# ProDocument_AD9744_2025-01-04.net
KiCad netlist of a schematic drawn in EasyEDA Pro
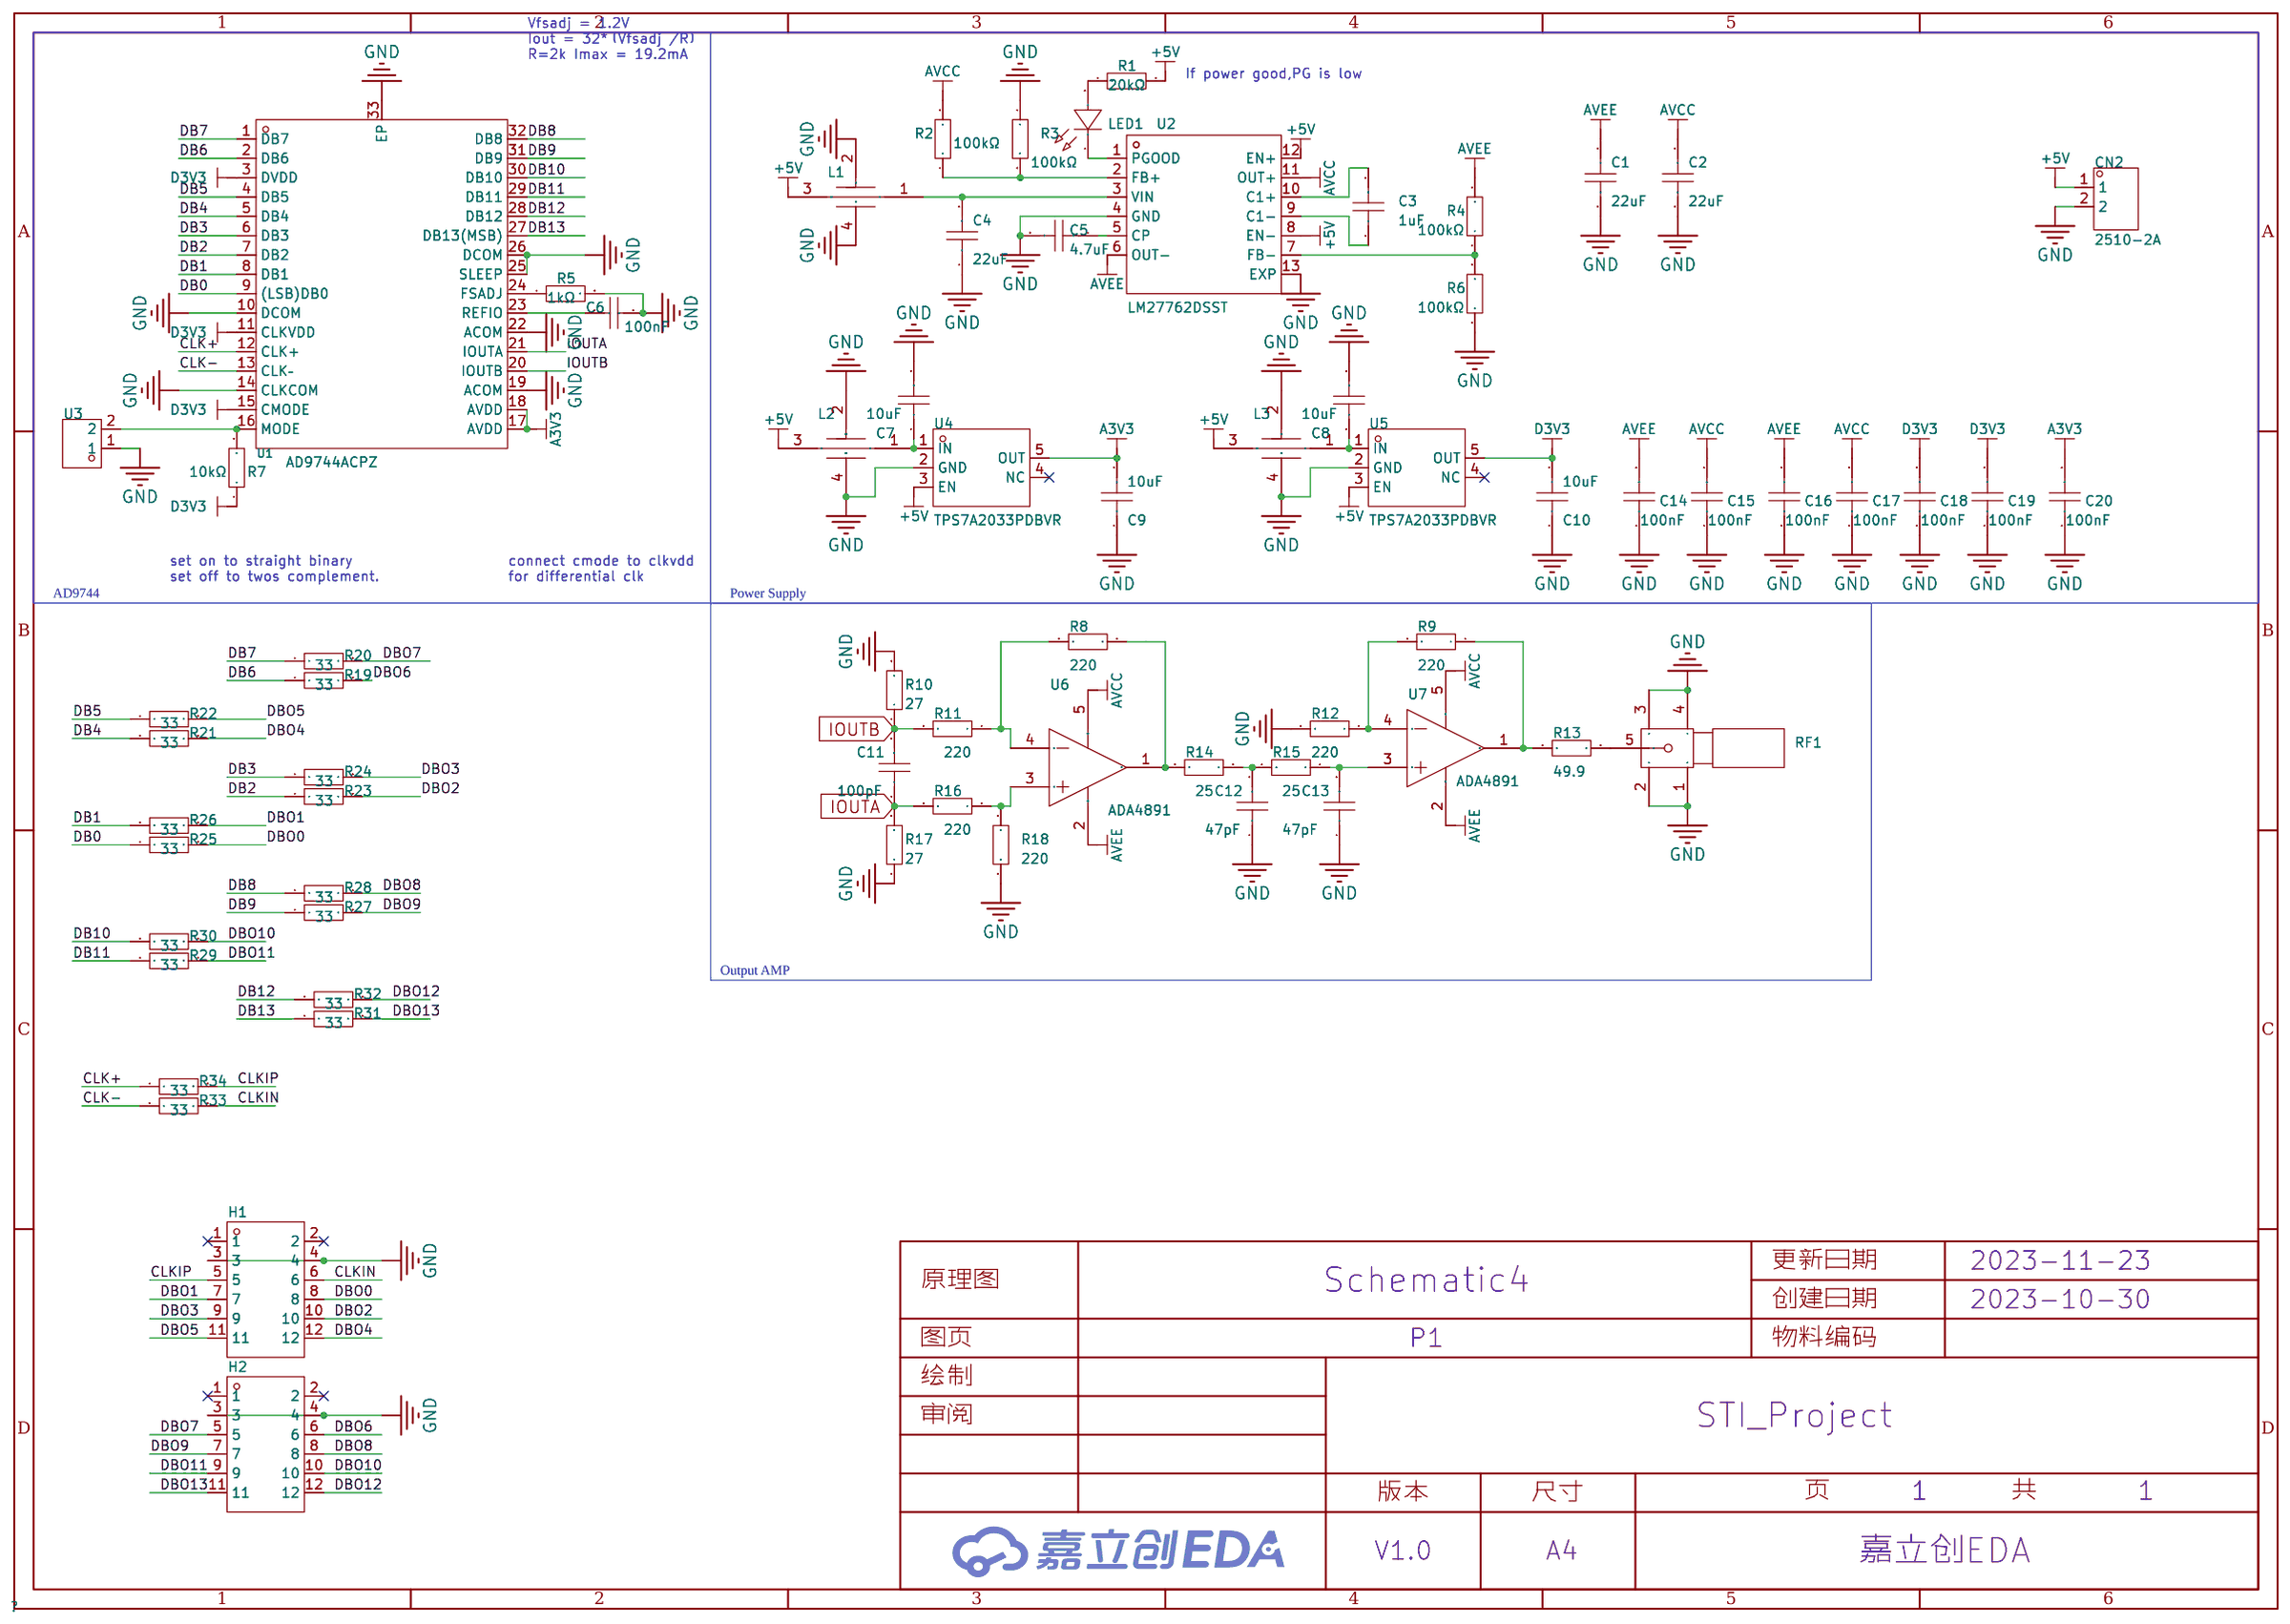
[diagram p0: schematic sheet]

(export (version "E")
  (design (tool "Eeschema 10.0.6"))
  (components
    (comp (ref "C1")
      (value "22uF")
      (footprint "easyedapro:C0805")
      (description "容值:22uF;精度:±20%;额定电压:25V;材质(温度系数):X5R;")
      (fields
        (field (name "Manufacturer Part") "CL21A226MAQNNNE")
        (field (name "Manufacturer") "SAMSUNG(三星)")
      )
      (libsource (lib "easyedapro") (part "CL21A226MAQNNNE"))
    )
    (comp (ref "C2")
      (value "22uF")
      (footprint "easyedapro:C0805")
      (description "容值:22uF;精度:±20%;额定电压:25V;材质(温度系数):X5R;")
      (fields
        (field (name "Manufacturer Part") "CL21A226MAQNNNE")
        (field (name "Manufacturer") "SAMSUNG(三星)")
      )
      (libsource (lib "easyedapro") (part "CL21A226MAQNNNE"))
    )
    (comp (ref "C3")
      (value "1uF")
      (footprint "easyedapro:C0402")
      (libsource (lib "easyedapro") (part "CapAcitance"))
    )
    (comp (ref "C4")
      (value "22uF")
      (footprint "easyedapro:C0805")
      (description "容值:22uF;精度:±20%;额定电压:25V;材质(温度系数):X5R;")
      (fields
        (field (name "Manufacturer Part") "CL21A226MAQNNNE")
        (field (name "Manufacturer") "SAMSUNG(三星)")
      )
      (libsource (lib "easyedapro") (part "CL21A226MAQNNNE"))
    )
    (comp (ref "C5")
      (value "4.7uF")
      (footprint "easyedapro:C0402")
      (libsource (lib "easyedapro") (part "CapAcitance"))
    )
    (comp (ref "C6")
      (value "100nF")
      (footprint "easyedapro:C0402")
      (description "容值:100nF;精度:±10%;额定电压:16V;材质(温度系数):X7R;")
      (fields
        (field (name "Manufacturer Part") "CL05B104KO5NNNC")
        (field (name "Manufacturer") "SAMSUNG(三星)")
      )
      (libsource (lib "easyedapro") (part "CL05B104KO5NNNC"))
    )
    (comp (ref "C7")
      (value "10uF")
      (footprint "easyedapro:C0402")
      (libsource (lib "easyedapro") (part "CapAcitance"))
    )
    (comp (ref "C8")
      (value "10uF")
      (footprint "easyedapro:C0402")
      (libsource (lib "easyedapro") (part "CapAcitance"))
    )
    (comp (ref "C9")
      (value "10uF")
      (footprint "easyedapro:C0402")
      (libsource (lib "easyedapro") (part "CapAcitance"))
    )
    (comp (ref "C10")
      (value "10uF")
      (footprint "easyedapro:C0402")
      (libsource (lib "easyedapro") (part "CapAcitance"))
    )
    (comp (ref "C11")
      (value "100pF")
      (footprint "easyedapro:C0402")
      (libsource (lib "easyedapro") (part "CapAcitance"))
    )
    (comp (ref "C12")
      (value "47pF")
      (footprint "easyedapro:C0402")
      (libsource (lib "easyedapro") (part "CapAcitance"))
    )
    (comp (ref "C13")
      (value "47pF")
      (footprint "easyedapro:C0402")
      (libsource (lib "easyedapro") (part "CapAcitance"))
    )
    (comp (ref "C14")
      (value "100nF")
      (footprint "easyedapro:C0402")
      (libsource (lib "easyedapro") (part "CapAcitance"))
    )
    (comp (ref "C15")
      (value "100nF")
      (footprint "easyedapro:C0402")
      (libsource (lib "easyedapro") (part "CapAcitance"))
    )
    (comp (ref "C16")
      (value "100nF")
      (footprint "easyedapro:C0402")
      (libsource (lib "easyedapro") (part "CapAcitance"))
    )
    (comp (ref "C17")
      (value "100nF")
      (footprint "easyedapro:C0402")
      (libsource (lib "easyedapro") (part "CapAcitance"))
    )
    (comp (ref "C18")
      (value "100nF")
      (footprint "easyedapro:C0402")
      (libsource (lib "easyedapro") (part "CapAcitance"))
    )
    (comp (ref "C19")
      (value "100nF")
      (footprint "easyedapro:C0402")
      (libsource (lib "easyedapro") (part "CapAcitance"))
    )
    (comp (ref "C20")
      (value "100nF")
      (footprint "easyedapro:C0402")
      (libsource (lib "easyedapro") (part "CapAcitance"))
    )
    (comp (ref "CN2")
      (value "2510-2A")
      (footprint "easyedapro:CONN-TH_KF2510-2A")
      (description "参考系列:-;间距:2.54mm;插针结构:1x2P;排数:1;每排PIN数:2;行距:-;安装方式:-;触头材质:-;")
      (fields (field (name "Manufacturer") "BOOMELE(博穆精密)"))
      (libsource (lib "easyedapro") (part "KF2510-2A"))
    )
    (comp (ref "H1")
      (value "DZ254W-22-12-69")
      (footprint "easyedapro:HDR-TH_12P-P2.54-H-M-R2-C6-S2.54-W12.5")
      (fields (field (name "Manufacturer") "DEALON(德艺隆)"))
      (libsource (lib "easyedapro") (part "DZ254W-22-12-69"))
    )
    (comp (ref "H2")
      (value "DZ254W-22-12-69")
      (footprint "easyedapro:HDR-TH_12P-P2.54-H-M-R2-C6-S2.54-W12.5")
      (fields (field (name "Manufacturer") "DEALON(德艺隆)"))
      (libsource (lib "easyedapro") (part "DZ254W-22-12-69"))
    )
    (comp (ref "L1")
      (value "NFM21PC104R1E3D")
      (footprint "easyedapro:CAP-SMD_4P-L2.0-W1.25")
      (description "电容量:100nF;精度:±20%;直流电阻:30mΩ;")
      (fields (field (name "Manufacturer") "muRata(村田)"))
      (libsource (lib "easyedapro") (part "NFM21PC104R1E3D"))
    )
    (comp (ref "L2")
      (value "NFM21PC104R1E3D")
      (footprint "easyedapro:CAP-SMD_4P-L2.0-W1.25")
      (description "电容量:100nF;精度:±20%;直流电阻:30mΩ;")
      (fields (field (name "Manufacturer") "muRata(村田)"))
      (libsource (lib "easyedapro") (part "NFM21PC104R1E3D"))
    )
    (comp (ref "L3")
      (value "NFM21PC104R1E3D")
      (footprint "easyedapro:CAP-SMD_4P-L2.0-W1.25")
      (description "电容量:100nF;精度:±20%;直流电阻:30mΩ;")
      (fields (field (name "Manufacturer") "muRata(村田)"))
      (libsource (lib "easyedapro") (part "NFM21PC104R1E3D"))
    )
    (comp (ref "LED1")
      (value "VLMTG1401-GS08")
      (footprint "easyedapro:LED0603-RD_GREEN")
      (description "发光颜色:翠绿;二极管配置:-;主波长:525nm;色温:-;功率:64mW;安装方式:-;")
      (fields (field (name "Manufacturer") "VISHAY(威世)"))
      (libsource (lib "easyedapro") (part "VLMTG1401-GS08"))
    )
    (comp (ref "R1")
      (value "20kΩ")
      (footprint "easyedapro:R0402")
      (description "电阻类型:厚膜电阻;阻值:1kΩ;精度:±1%;功率:62.5mW;")
      (fields
        (field (name "Manufacturer Part") "0402WGF1001TCE")
        (field (name "Manufacturer") "UNI-ROYAL(厚声)")
      )
      (libsource (lib "easyedapro") (part "0402WGF1001TCE"))
    )
    (comp (ref "R2")
      (value "100kΩ")
      (footprint "easyedapro:R0402")
      (description "电阻类型:厚膜电阻;阻值:1kΩ;精度:±1%;功率:62.5mW;")
      (fields
        (field (name "Manufacturer Part") "0402WGF1001TCE")
        (field (name "Manufacturer") "UNI-ROYAL(厚声)")
      )
      (libsource (lib "easyedapro") (part "0402WGF1001TCE"))
    )
    (comp (ref "R3")
      (value "100kΩ")
      (footprint "easyedapro:R0402")
      (description "电阻类型:厚膜电阻;阻值:1kΩ;精度:±1%;功率:62.5mW;")
      (fields
        (field (name "Manufacturer Part") "0402WGF1001TCE")
        (field (name "Manufacturer") "UNI-ROYAL(厚声)")
      )
      (libsource (lib "easyedapro") (part "0402WGF1001TCE"))
    )
    (comp (ref "R4")
      (value "100kΩ")
      (footprint "easyedapro:R0402")
      (description "电阻类型:厚膜电阻;阻值:1kΩ;精度:±1%;功率:62.5mW;")
      (fields
        (field (name "Manufacturer Part") "0402WGF1001TCE")
        (field (name "Manufacturer") "UNI-ROYAL(厚声)")
      )
      (libsource (lib "easyedapro") (part "0402WGF1001TCE"))
    )
    (comp (ref "R5")
      (value "1kΩ")
      (footprint "easyedapro:R0402")
      (description "电阻类型:厚膜电阻;阻值:1kΩ;精度:±1%;功率:62.5mW;")
      (fields
        (field (name "Manufacturer Part") "0402WGF1001TCE")
        (field (name "Manufacturer") "UNI-ROYAL(厚声)")
      )
      (libsource (lib "easyedapro") (part "0402WGF1001TCE"))
    )
    (comp (ref "R6")
      (value "100kΩ")
      (footprint "easyedapro:R0402")
      (description "电阻类型:厚膜电阻;阻值:1kΩ;精度:±1%;功率:62.5mW;")
      (fields
        (field (name "Manufacturer Part") "0402WGF1001TCE")
        (field (name "Manufacturer") "UNI-ROYAL(厚声)")
      )
      (libsource (lib "easyedapro") (part "0402WGF1001TCE"))
    )
    (comp (ref "R7")
      (value "10kΩ")
      (footprint "easyedapro:R0402")
      (description "电阻类型:厚膜电阻;阻值:1kΩ;精度:±1%;功率:62.5mW;")
      (fields
        (field (name "Manufacturer Part") "0402WGF1001TCE")
        (field (name "Manufacturer") "UNI-ROYAL(厚声)")
      )
      (libsource (lib "easyedapro") (part "0402WGF1001TCE"))
    )
    (comp (ref "R8") (value "220") (footprint "easyedapro:R0402") (libsource (lib "easyedapro") (part "电阻")))
    (comp (ref "R9") (value "220") (footprint "easyedapro:R0402") (libsource (lib "easyedapro") (part "电阻")))
    (comp (ref "R10") (value "27") (footprint "easyedapro:R0402") (libsource (lib "easyedapro") (part "电阻")))
    (comp (ref "R11") (value "220") (footprint "easyedapro:R0402") (libsource (lib "easyedapro") (part "电阻")))
    (comp (ref "R12") (value "220") (footprint "easyedapro:R0402") (libsource (lib "easyedapro") (part "电阻")))
    (comp (ref "R13")
      (value "49.9")
      (footprint "easyedapro:R0402")
      (libsource (lib "easyedapro") (part "电阻"))
    )
    (comp (ref "R14") (value "25") (footprint "easyedapro:R0402") (libsource (lib "easyedapro") (part "电阻")))
    (comp (ref "R15") (value "25") (footprint "easyedapro:R0402") (libsource (lib "easyedapro") (part "电阻")))
    (comp (ref "R16") (value "220") (footprint "easyedapro:R0402") (libsource (lib "easyedapro") (part "电阻")))
    (comp (ref "R17") (value "27") (footprint "easyedapro:R0402") (libsource (lib "easyedapro") (part "电阻")))
    (comp (ref "R18") (value "220") (footprint "easyedapro:R0402") (libsource (lib "easyedapro") (part "电阻")))
    (comp (ref "R19") (value "33") (footprint "easyedapro:R0402") (libsource (lib "easyedapro") (part "电阻")))
    (comp (ref "R20") (value "33") (footprint "easyedapro:R0402") (libsource (lib "easyedapro") (part "电阻")))
    (comp (ref "R21") (value "33") (footprint "easyedapro:R0402") (libsource (lib "easyedapro") (part "电阻")))
    (comp (ref "R22") (value "33") (footprint "easyedapro:R0402") (libsource (lib "easyedapro") (part "电阻")))
    (comp (ref "R23") (value "33") (footprint "easyedapro:R0402") (libsource (lib "easyedapro") (part "电阻")))
    (comp (ref "R24") (value "33") (footprint "easyedapro:R0402") (libsource (lib "easyedapro") (part "电阻")))
    (comp (ref "R25") (value "33") (footprint "easyedapro:R0402") (libsource (lib "easyedapro") (part "电阻")))
    (comp (ref "R26") (value "33") (footprint "easyedapro:R0402") (libsource (lib "easyedapro") (part "电阻")))
    (comp (ref "R27") (value "33") (footprint "easyedapro:R0402") (libsource (lib "easyedapro") (part "电阻")))
    (comp (ref "R28") (value "33") (footprint "easyedapro:R0402") (libsource (lib "easyedapro") (part "电阻")))
    (comp (ref "R29") (value "33") (footprint "easyedapro:R0402") (libsource (lib "easyedapro") (part "电阻")))
    (comp (ref "R30") (value "33") (footprint "easyedapro:R0402") (libsource (lib "easyedapro") (part "电阻")))
    (comp (ref "R31") (value "33") (footprint "easyedapro:R0402") (libsource (lib "easyedapro") (part "电阻")))
    (comp (ref "R32") (value "33") (footprint "easyedapro:R0402") (libsource (lib "easyedapro") (part "电阻")))
    (comp (ref "R33") (value "33") (footprint "easyedapro:R0402") (libsource (lib "easyedapro") (part "电阻")))
    (comp (ref "R34") (value "33") (footprint "easyedapro:R0402") (libsource (lib "easyedapro") (part "电阻")))
    (comp (ref "RF1")
      (value "BWSMA-KWE-Z001")
      (footprint "easyedapro:SMA-TH_BWSMA-KWE-Z001")
      (description "连接器类型:板端;射频系列:SMA;接口类型:内孔;端口数量:1;阻抗:50Ω;频率-最大值:12.4GHz;样式:弯头;接口直径:5.3mm;接口长度/高度:-;工作温度范围:-;")
      (fields (field (name "Manufacturer") "BAT WIRELESS(蝙蝠无线)"))
      (libsource (lib "easyedapro") (part "BWSMA-KWE-Z001"))
    )
    (comp (ref "U1")
      (value "AD9744ACPZ")
      (footprint "easyedapro:LFCSP-32_L5.0-W5.0-P0.50-TL-EP3.1")
      (description "接口:并行;分辨率:14位;稳定时间:11ns;INL/DNL:±0.5LSB；±0.8LSB;电源电压:2.7V~3.6V;")
      (fields (field (name "Manufacturer") "ADI(亚德诺)"))
      (libsource (lib "easyedapro") (part "AD9744ACPZ"))
    )
    (comp (ref "U2")
      (value "LM27762DSST")
      (footprint "easyedapro:WSON-12_L2.0-W3.0-P0.50-BL-EP")
      (description "功能类型:电荷泵;同步整流:否;输出通道数:2;拓扑结构:-;输入电压:2.7V~5.5V;输出电压:-5V~-1.5V；1.5V~5V;输出电流(最大值):250mA;开关频率:2.3MHz;")
      (fields (field (name "Manufacturer") "TI(德州仪器)"))
      (libsource (lib "easyedapro") (part "LM27762DSST"))
    )
    (comp (ref "U3")
      (value "SIP2-2.54mm单排针")
      (footprint "easyedapro:HDR-TH_2P-P2.54-V-M-1")
      (libsource (lib "easyedapro") (part "SIP2-2.54MM单排针"))
    )
    (comp (ref "U4")
      (value "TPS7A2033PDBVR")
      (footprint "easyedapro:SOT-23-5_L2.9-W1.6-P0.95-LS2.8-BR")
      (fields (field (name "Manufacturer") "TI(德州仪器)"))
      (libsource (lib "easyedapro") (part "TPS7A2033PDBVR"))
    )
    (comp (ref "U5")
      (value "TPS7A2033PDBVR")
      (footprint "easyedapro:SOT-23-5_L2.9-W1.6-P0.95-LS2.8-BR")
      (fields (field (name "Manufacturer") "TI(德州仪器)"))
      (libsource (lib "easyedapro") (part "TPS7A2033PDBVR"))
    )
    (comp (ref "U6")
      (value "ADA4891")
      (footprint "easyedapro:SOT-23-5_L3.0-W1.7-P0.95-LS2.8-BR")
      (fields (field (name "Manufacturer") "ADI(亚德诺)/LINEAR(凌特)"))
      (libsource (lib "easyedapro") (part "ADA4891-1ARJZ-R7"))
    )
    (comp (ref "U7")
      (value "ADA4891")
      (footprint "easyedapro:SOT-23-5_L3.0-W1.7-P0.95-LS2.8-BR")
      (fields (field (name "Manufacturer") "ADI(亚德诺)/LINEAR(凌特)"))
      (libsource (lib "easyedapro") (part "ADA4891-1ARJZ-R7"))
    )
  )
  (nets
    (net (code "1") (name "+5V") (class "Default")
      (node (ref "CN2") (pin "1") (pinfunction "1_1") (pintype "unspecified"))
      (node (ref "L1") (pin "3") (pinfunction "OUT_3") (pintype "input"))
      (node (ref "L2") (pin "3") (pinfunction "OUT_3") (pintype "input"))
      (node (ref "L3") (pin "3") (pinfunction "OUT_3") (pintype "input"))
      (node (ref "R1") (pin "2") (pinfunction "2_2") (pintype "input"))
      (node (ref "U2") (pin "12") (pinfunction "EN+_12") (pintype "input"))
      (node (ref "U2") (pin "8") (pinfunction "EN-_8") (pintype "input"))
      (node (ref "U4") (pin "3") (pinfunction "EN_3") (pintype "input"))
      (node (ref "U5") (pin "3") (pinfunction "EN_3") (pintype "input"))
    )
    (net (code "2") (name "/CLK+") (class "Default")
      (node (ref "R33") (pin "1") (pinfunction "1_1") (pintype "input"))
      (node (ref "U1") (pin "12") (pinfunction "CLK+_12") (pintype "input"))
    )
    (net (code "3") (name "/CLK-") (class "Default")
      (node (ref "R34") (pin "1") (pinfunction "1_1") (pintype "input"))
      (node (ref "U1") (pin "13") (pinfunction "CLK–_13") (pintype "input"))
    )
    (net (code "4") (name "/CLKIN") (class "Default")
      (node (ref "H1") (pin "6") (pinfunction "6_6") (pintype "input"))
      (node (ref "R34") (pin "2") (pinfunction "2_2") (pintype "input"))
    )
    (net (code "5") (name "/CLKIP") (class "Default")
      (node (ref "H1") (pin "5") (pinfunction "5_5") (pintype "input"))
      (node (ref "R33") (pin "2") (pinfunction "2_2") (pintype "input"))
    )
    (net (code "6") (name "/DB0") (class "Default")
      (node (ref "R26") (pin "1") (pinfunction "1_1") (pintype "input"))
      (node (ref "U1") (pin "9") (pinfunction "(LSB)DB0_9") (pintype "input"))
    )
    (net (code "7") (name "/DB1") (class "Default")
      (node (ref "R25") (pin "1") (pinfunction "1_1") (pintype "input"))
      (node (ref "U1") (pin "8") (pinfunction "DB1_8") (pintype "input"))
    )
    (net (code "8") (name "/DB2") (class "Default")
      (node (ref "R24") (pin "1") (pinfunction "1_1") (pintype "input"))
      (node (ref "U1") (pin "7") (pinfunction "DB2_7") (pintype "input"))
    )
    (net (code "9") (name "/DB3") (class "Default")
      (node (ref "R23") (pin "1") (pinfunction "1_1") (pintype "input"))
      (node (ref "U1") (pin "6") (pinfunction "DB3_6") (pintype "input"))
    )
    (net (code "10") (name "/DB4") (class "Default")
      (node (ref "R22") (pin "1") (pinfunction "1_1") (pintype "input"))
      (node (ref "U1") (pin "5") (pinfunction "DB4_5") (pintype "input"))
    )
    (net (code "11") (name "/DB5") (class "Default")
      (node (ref "R21") (pin "1") (pinfunction "1_1") (pintype "input"))
      (node (ref "U1") (pin "4") (pinfunction "DB5_4") (pintype "input"))
    )
    (net (code "12") (name "/DB6") (class "Default")
      (node (ref "R20") (pin "1") (pinfunction "1_1") (pintype "input"))
      (node (ref "U1") (pin "2") (pinfunction "DB6_2") (pintype "input"))
    )
    (net (code "13") (name "/DB7") (class "Default")
      (node (ref "R19") (pin "1") (pinfunction "1_1") (pintype "input"))
      (node (ref "U1") (pin "1") (pinfunction "DB7_1") (pintype "input"))
    )
    (net (code "14") (name "/DB8") (class "Default")
      (node (ref "R27") (pin "1") (pinfunction "1_1") (pintype "input"))
      (node (ref "U1") (pin "32") (pinfunction "DB8_32") (pintype "input"))
    )
    (net (code "15") (name "/DB9") (class "Default")
      (node (ref "R28") (pin "1") (pinfunction "1_1") (pintype "input"))
      (node (ref "U1") (pin "31") (pinfunction "DB9_31") (pintype "input"))
    )
    (net (code "16") (name "/DB10") (class "Default")
      (node (ref "R29") (pin "1") (pinfunction "1_1") (pintype "input"))
      (node (ref "U1") (pin "30") (pinfunction "DB10_30") (pintype "input"))
    )
    (net (code "17") (name "/DB11") (class "Default")
      (node (ref "R30") (pin "1") (pinfunction "1_1") (pintype "input"))
      (node (ref "U1") (pin "29") (pinfunction "DB11_29") (pintype "input"))
    )
    (net (code "18") (name "/DB12") (class "Default")
      (node (ref "R31") (pin "1") (pinfunction "1_1") (pintype "input"))
      (node (ref "U1") (pin "28") (pinfunction "DB12_28") (pintype "input"))
    )
    (net (code "19") (name "/DB13") (class "Default")
      (node (ref "R32") (pin "1") (pinfunction "1_1") (pintype "input"))
      (node (ref "U1") (pin "27") (pinfunction "DB13(MSB)_27") (pintype "input"))
    )
    (net (code "20") (name "/DBO0") (class "Default")
      (node (ref "H1") (pin "8") (pinfunction "8_8") (pintype "input"))
      (node (ref "R26") (pin "2") (pinfunction "2_2") (pintype "input"))
    )
    (net (code "21") (name "/DBO1") (class "Default")
      (node (ref "H1") (pin "7") (pinfunction "7_7") (pintype "input"))
      (node (ref "R25") (pin "2") (pinfunction "2_2") (pintype "input"))
    )
    (net (code "22") (name "/DBO2") (class "Default")
      (node (ref "H1") (pin "10") (pinfunction "10_10") (pintype "input"))
      (node (ref "R24") (pin "2") (pinfunction "2_2") (pintype "input"))
    )
    (net (code "23") (name "/DBO3") (class "Default")
      (node (ref "H1") (pin "9") (pinfunction "9_9") (pintype "input"))
      (node (ref "R23") (pin "2") (pinfunction "2_2") (pintype "input"))
    )
    (net (code "24") (name "/DBO4") (class "Default")
      (node (ref "H1") (pin "12") (pinfunction "12_12") (pintype "input"))
      (node (ref "R22") (pin "2") (pinfunction "2_2") (pintype "input"))
    )
    (net (code "25") (name "/DBO5") (class "Default")
      (node (ref "H1") (pin "11") (pinfunction "11_11") (pintype "input"))
      (node (ref "R21") (pin "2") (pinfunction "2_2") (pintype "input"))
    )
    (net (code "26") (name "/DBO6") (class "Default")
      (node (ref "H2") (pin "6") (pinfunction "6_6") (pintype "input"))
      (node (ref "R20") (pin "2") (pinfunction "2_2") (pintype "input"))
    )
    (net (code "27") (name "/DBO7") (class "Default")
      (node (ref "H2") (pin "5") (pinfunction "5_5") (pintype "input"))
      (node (ref "R19") (pin "2") (pinfunction "2_2") (pintype "input"))
    )
    (net (code "28") (name "/DBO8") (class "Default")
      (node (ref "H2") (pin "8") (pinfunction "8_8") (pintype "input"))
      (node (ref "R27") (pin "2") (pinfunction "2_2") (pintype "input"))
    )
    (net (code "29") (name "/DBO9") (class "Default")
      (node (ref "H2") (pin "7") (pinfunction "7_7") (pintype "input"))
      (node (ref "R28") (pin "2") (pinfunction "2_2") (pintype "input"))
    )
    (net (code "30") (name "/DBO10") (class "Default")
      (node (ref "H2") (pin "10") (pinfunction "10_10") (pintype "input"))
      (node (ref "R29") (pin "2") (pinfunction "2_2") (pintype "input"))
    )
    (net (code "31") (name "/DBO11") (class "Default")
      (node (ref "H2") (pin "9") (pinfunction "9_9") (pintype "input"))
      (node (ref "R30") (pin "2") (pinfunction "2_2") (pintype "input"))
    )
    (net (code "32") (name "/DBO12") (class "Default")
      (node (ref "H2") (pin "12") (pinfunction "12_12") (pintype "input"))
      (node (ref "R31") (pin "2") (pinfunction "2_2") (pintype "input"))
    )
    (net (code "33") (name "/DBO13") (class "Default")
      (node (ref "H2") (pin "11") (pinfunction "11_11") (pintype "input"))
      (node (ref "R32") (pin "2") (pinfunction "2_2") (pintype "input"))
    )
    (net (code "34") (name "A3V3") (class "Default")
      (node (ref "C20") (pin "2") (pinfunction "2_2") (pintype "input"))
      (node (ref "C9") (pin "2") (pinfunction "2_2") (pintype "input"))
      (node (ref "U1") (pin "17") (pinfunction "AVDD_17") (pintype "input"))
      (node (ref "U1") (pin "18") (pinfunction "AVDD_18") (pintype "input"))
      (node (ref "U4") (pin "5") (pinfunction "OUT_5") (pintype "input"))
    )
    (net (code "35") (name "AVCC") (class "Default")
      (node (ref "C15") (pin "2") (pinfunction "2_2") (pintype "input"))
      (node (ref "C17") (pin "2") (pinfunction "2_2") (pintype "input"))
      (node (ref "C2") (pin "2") (pinfunction "2_2") (pintype "input"))
      (node (ref "R2") (pin "2") (pinfunction "2_2") (pintype "input"))
      (node (ref "U2") (pin "11") (pinfunction "OUT+_11") (pintype "input"))
      (node (ref "U6") (pin "5") (pinfunction "+VS_5") (pintype "input"))
      (node (ref "U7") (pin "5") (pinfunction "+VS_5") (pintype "input"))
    )
    (net (code "36") (name "AVEE") (class "Default")
      (node (ref "C1") (pin "2") (pinfunction "2_2") (pintype "input"))
      (node (ref "C14") (pin "2") (pinfunction "2_2") (pintype "input"))
      (node (ref "C16") (pin "2") (pinfunction "2_2") (pintype "input"))
      (node (ref "R4") (pin "2") (pinfunction "2_2") (pintype "input"))
      (node (ref "U2") (pin "6") (pinfunction "OUT-_6") (pintype "input"))
      (node (ref "U6") (pin "2") (pinfunction "-VS_2") (pintype "input"))
      (node (ref "U7") (pin "2") (pinfunction "-VS_2") (pintype "input"))
    )
    (net (code "37") (name "D3V3") (class "Default")
      (node (ref "C10") (pin "2") (pinfunction "2_2") (pintype "input"))
      (node (ref "C18") (pin "2") (pinfunction "2_2") (pintype "input"))
      (node (ref "C19") (pin "2") (pinfunction "2_2") (pintype "input"))
      (node (ref "R7") (pin "1") (pinfunction "1_1") (pintype "input"))
      (node (ref "U1") (pin "11") (pinfunction "CLKVDD_11") (pintype "input"))
      (node (ref "U1") (pin "15") (pinfunction "CMODE_15") (pintype "input"))
      (node (ref "U1") (pin "3") (pinfunction "DVDD_3") (pintype "input"))
      (node (ref "U5") (pin "5") (pinfunction "OUT_5") (pintype "input"))
    )
    (net (code "38") (name "GND") (class "Default")
      (node (ref "C1") (pin "1") (pinfunction "1_1") (pintype "input"))
      (node (ref "C10") (pin "1") (pinfunction "1_1") (pintype "input"))
      (node (ref "C12") (pin "1") (pinfunction "1_1") (pintype "input"))
      (node (ref "C13") (pin "1") (pinfunction "1_1") (pintype "input"))
      (node (ref "C14") (pin "1") (pinfunction "1_1") (pintype "input"))
      (node (ref "C15") (pin "1") (pinfunction "1_1") (pintype "input"))
      (node (ref "C16") (pin "1") (pinfunction "1_1") (pintype "input"))
      (node (ref "C17") (pin "1") (pinfunction "1_1") (pintype "input"))
      (node (ref "C18") (pin "1") (pinfunction "1_1") (pintype "input"))
      (node (ref "C19") (pin "1") (pinfunction "1_1") (pintype "input"))
      (node (ref "C2") (pin "1") (pinfunction "1_1") (pintype "input"))
      (node (ref "C20") (pin "1") (pinfunction "1_1") (pintype "input"))
      (node (ref "C4") (pin "1") (pinfunction "1_1") (pintype "input"))
      (node (ref "C5") (pin "2") (pinfunction "2_2") (pintype "input"))
      (node (ref "C6") (pin "2") (pinfunction "2_2") (pintype "input"))
      (node (ref "C7") (pin "2") (pinfunction "2_2") (pintype "input"))
      (node (ref "C8") (pin "2") (pinfunction "2_2") (pintype "input"))
      (node (ref "C9") (pin "1") (pinfunction "1_1") (pintype "input"))
      (node (ref "CN2") (pin "2") (pinfunction "2_2") (pintype "unspecified"))
      (node (ref "H1") (pin "3") (pinfunction "3_3") (pintype "input"))
      (node (ref "H1") (pin "4") (pinfunction "4_4") (pintype "input"))
      (node (ref "H2") (pin "3") (pinfunction "3_3") (pintype "input"))
      (node (ref "H2") (pin "4") (pinfunction "4_4") (pintype "input"))
      (node (ref "L1") (pin "2") (pinfunction "GND_2") (pintype "input"))
      (node (ref "L1") (pin "4") (pinfunction "GND_4") (pintype "input"))
      (node (ref "L2") (pin "2") (pinfunction "GND_2") (pintype "input"))
      (node (ref "L2") (pin "4") (pinfunction "GND_4") (pintype "input"))
      (node (ref "L3") (pin "2") (pinfunction "GND_2") (pintype "input"))
      (node (ref "L3") (pin "4") (pinfunction "GND_4") (pintype "input"))
      (node (ref "R10") (pin "2") (pinfunction "2_2") (pintype "input"))
      (node (ref "R12") (pin "2") (pinfunction "2_2") (pintype "input"))
      (node (ref "R17") (pin "1") (pinfunction "1_1") (pintype "input"))
      (node (ref "R18") (pin "2") (pinfunction "2_2") (pintype "input"))
      (node (ref "R3") (pin "1") (pinfunction "1_1") (pintype "input"))
      (node (ref "R5") (pin "2") (pinfunction "2_2") (pintype "input"))
      (node (ref "R6") (pin "1") (pinfunction "1_1") (pintype "input"))
      (node (ref "RF1") (pin "1") (pinfunction "1_1") (pintype "input"))
      (node (ref "RF1") (pin "2") (pinfunction "2_2") (pintype "input"))
      (node (ref "RF1") (pin "3") (pinfunction "3_3") (pintype "input"))
      (node (ref "RF1") (pin "4") (pinfunction "4_4") (pintype "input"))
      (node (ref "U1") (pin "10") (pinfunction "DCOM_10") (pintype "input"))
      (node (ref "U1") (pin "14") (pinfunction "CLKCOM_14") (pintype "input"))
      (node (ref "U1") (pin "19") (pinfunction "ACOM_19") (pintype "input"))
      (node (ref "U1") (pin "22") (pinfunction "ACOM_22") (pintype "input"))
      (node (ref "U1") (pin "25") (pinfunction "SLEEP_25") (pintype "input"))
      (node (ref "U1") (pin "26") (pinfunction "DCOM_26") (pintype "input"))
      (node (ref "U1") (pin "33") (pinfunction "EP_33") (pintype "input"))
      (node (ref "U2") (pin "13") (pinfunction "EXP_13") (pintype "input"))
      (node (ref "U2") (pin "4") (pinfunction "GND_4") (pintype "input"))
      (node (ref "U3") (pin "1") (pinfunction "1_1") (pintype "input"))
      (node (ref "U4") (pin "2") (pinfunction "GND_2") (pintype "input"))
      (node (ref "U5") (pin "2") (pinfunction "GND_2") (pintype "input"))
    )
    (net (code "39") (name "IOUTA") (class "Default")
      (node (ref "C11") (pin "1") (pinfunction "1_1") (pintype "input"))
      (node (ref "R16") (pin "2") (pinfunction "2_2") (pintype "input"))
      (node (ref "R17") (pin "2") (pinfunction "2_2") (pintype "input"))
      (node (ref "U1") (pin "21") (pinfunction "IOUTA_21") (pintype "input"))
    )
    (net (code "40") (name "IOUTB") (class "Default")
      (node (ref "C11") (pin "2") (pinfunction "2_2") (pintype "input"))
      (node (ref "R10") (pin "1") (pinfunction "1_1") (pintype "input"))
      (node (ref "R11") (pin "2") (pinfunction "2_2") (pintype "input"))
      (node (ref "U1") (pin "20") (pinfunction "IOUTB_20") (pintype "input"))
    )
    (net (code "41") (name "Net-(C12-Pad2)") (class "Default")
      (node (ref "C12") (pin "2") (pinfunction "2_2") (pintype "input"))
      (node (ref "R14") (pin "1") (pinfunction "1_1") (pintype "input"))
      (node (ref "R15") (pin "2") (pinfunction "2_2") (pintype "input"))
    )
    (net (code "42") (name "Net-(L1-IN)") (class "Default")
      (node (ref "C4") (pin "2") (pinfunction "2_2") (pintype "input"))
      (node (ref "L1") (pin "1") (pinfunction "IN_1") (pintype "input"))
      (node (ref "U2") (pin "3") (pinfunction "VIN_3") (pintype "input"))
    )
    (net (code "43") (name "Net-(L2-IN)") (class "Default")
      (node (ref "C7") (pin "1") (pinfunction "1_1") (pintype "input"))
      (node (ref "L2") (pin "1") (pinfunction "IN_1") (pintype "input"))
      (node (ref "U4") (pin "1") (pinfunction "IN_1") (pintype "input"))
    )
    (net (code "44") (name "Net-(L3-IN)") (class "Default")
      (node (ref "C8") (pin "1") (pinfunction "1_1") (pintype "input"))
      (node (ref "L3") (pin "1") (pinfunction "IN_1") (pintype "input"))
      (node (ref "U5") (pin "1") (pinfunction "IN_1") (pintype "input"))
    )
    (net (code "45") (name "Net-(LED1-A)") (class "Default")
      (node (ref "LED1") (pin "2") (pinfunction "A_2") (pintype "input"))
      (node (ref "R1") (pin "1") (pinfunction "1_1") (pintype "input"))
    )
    (net (code "46") (name "Net-(LED1-K)") (class "Default")
      (node (ref "LED1") (pin "1") (pinfunction "K_1") (pintype "input"))
      (node (ref "U2") (pin "1") (pinfunction "PGOOD_1") (pintype "input"))
    )
    (net (code "47") (name "Net-(R13-Pad2)") (class "Default")
      (node (ref "R13") (pin "2") (pinfunction "2_2") (pintype "input"))
      (node (ref "RF1") (pin "5") (pinfunction "5_5") (pintype "input"))
    )
    (net (code "48") (name "Net-(U1-FSADJ)") (class "Default")
      (node (ref "R5") (pin "1") (pinfunction "1_1") (pintype "input"))
      (node (ref "U1") (pin "24") (pinfunction "FSADJ_24") (pintype "input"))
    )
    (net (code "49") (name "Net-(U1-MODE)") (class "Default")
      (node (ref "R7") (pin "2") (pinfunction "2_2") (pintype "input"))
      (node (ref "U1") (pin "16") (pinfunction "MODE_16") (pintype "input"))
      (node (ref "U3") (pin "2") (pinfunction "2_2") (pintype "input"))
    )
    (net (code "50") (name "Net-(U1-REFIO)") (class "Default")
      (node (ref "C6") (pin "1") (pinfunction "1_1") (pintype "input"))
      (node (ref "U1") (pin "23") (pinfunction "REFIO_23") (pintype "input"))
    )
    (net (code "51") (name "Net-(U2-C1+)") (class "Default")
      (node (ref "C3") (pin "2") (pinfunction "2_2") (pintype "input"))
      (node (ref "U2") (pin "10") (pinfunction "C1+_10") (pintype "input"))
    )
    (net (code "52") (name "Net-(U2-C1-)") (class "Default")
      (node (ref "C3") (pin "1") (pinfunction "1_1") (pintype "input"))
      (node (ref "U2") (pin "9") (pinfunction "C1-_9") (pintype "input"))
    )
    (net (code "53") (name "Net-(U2-CP)") (class "Default")
      (node (ref "C5") (pin "1") (pinfunction "1_1") (pintype "input"))
      (node (ref "U2") (pin "5") (pinfunction "CP_5") (pintype "input"))
    )
    (net (code "54") (name "Net-(U2-FB+)") (class "Default")
      (node (ref "R2") (pin "1") (pinfunction "1_1") (pintype "input"))
      (node (ref "R3") (pin "2") (pinfunction "2_2") (pintype "input"))
      (node (ref "U2") (pin "2") (pinfunction "FB+_2") (pintype "input"))
    )
    (net (code "55") (name "Net-(U2-FB-)") (class "Default")
      (node (ref "R4") (pin "1") (pinfunction "1_1") (pintype "input"))
      (node (ref "R6") (pin "2") (pinfunction "2_2") (pintype "input"))
      (node (ref "U2") (pin "7") (pinfunction "FB-_7") (pintype "input"))
    )
    (net (code "56") (name "Net-(U6-+IN)") (class "Default")
      (node (ref "R16") (pin "1") (pinfunction "1_1") (pintype "input"))
      (node (ref "R18") (pin "1") (pinfunction "1_1") (pintype "input"))
      (node (ref "U6") (pin "3") (pinfunction "+IN_3") (pintype "input"))
    )
    (net (code "57") (name "Net-(U6--IN)") (class "Default")
      (node (ref "R11") (pin "1") (pinfunction "1_1") (pintype "input"))
      (node (ref "R8") (pin "2") (pinfunction "2_2") (pintype "input"))
      (node (ref "U6") (pin "4") (pinfunction "-IN_4") (pintype "input"))
    )
    (net (code "58") (name "Net-(U6-OUT)") (class "Default")
      (node (ref "R14") (pin "2") (pinfunction "2_2") (pintype "input"))
      (node (ref "R8") (pin "1") (pinfunction "1_1") (pintype "input"))
      (node (ref "U6") (pin "1") (pinfunction "OUT_1") (pintype "output"))
    )
    (net (code "59") (name "Net-(U7-+IN)") (class "Default")
      (node (ref "C13") (pin "2") (pinfunction "2_2") (pintype "input"))
      (node (ref "R15") (pin "1") (pinfunction "1_1") (pintype "input"))
      (node (ref "U7") (pin "3") (pinfunction "+IN_3") (pintype "input"))
    )
    (net (code "60") (name "Net-(U7--IN)") (class "Default")
      (node (ref "R12") (pin "1") (pinfunction "1_1") (pintype "input"))
      (node (ref "R9") (pin "2") (pinfunction "2_2") (pintype "input"))
      (node (ref "U7") (pin "4") (pinfunction "-IN_4") (pintype "input"))
    )
    (net (code "61") (name "Net-(U7-OUT)") (class "Default")
      (node (ref "R13") (pin "1") (pinfunction "1_1") (pintype "input"))
      (node (ref "R9") (pin "1") (pinfunction "1_1") (pintype "input"))
      (node (ref "U7") (pin "1") (pinfunction "OUT_1") (pintype "output"))
    )
    (net (code "62") (name "unconnected-(H1-Pad1)") (class "Default")
      (node (ref "H1") (pin "1") (pinfunction "1_1") (pintype "input+no_connect"))
    )
    (net (code "63") (name "unconnected-(H1-Pad2)") (class "Default")
      (node (ref "H1") (pin "2") (pinfunction "2_2") (pintype "input+no_connect"))
    )
    (net (code "64") (name "unconnected-(H2-Pad1)") (class "Default")
      (node (ref "H2") (pin "1") (pinfunction "1_1") (pintype "input+no_connect"))
    )
    (net (code "65") (name "unconnected-(H2-Pad2)") (class "Default")
      (node (ref "H2") (pin "2") (pinfunction "2_2") (pintype "input+no_connect"))
    )
    (net (code "66") (name "unconnected-(U4-NC-Pad4)") (class "Default")
      (node (ref "U4") (pin "4") (pinfunction "NC_4") (pintype "input+no_connect"))
    )
    (net (code "67") (name "unconnected-(U5-NC-Pad4)") (class "Default")
      (node (ref "U5") (pin "4") (pinfunction "NC_4") (pintype "input+no_connect"))
    )
  )
)
